# S3C_MuxJTAG.net
KiCad netlist of a schematic drawn in Altium Designer
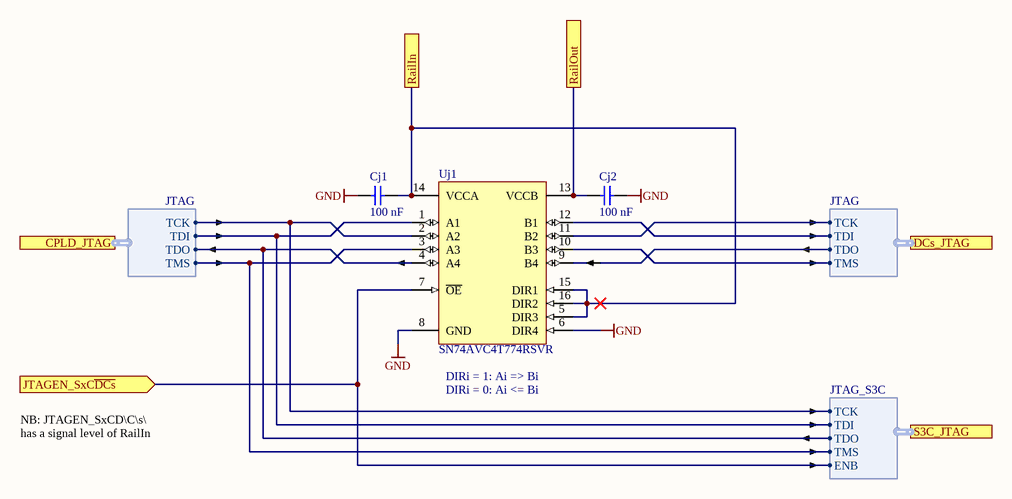
[diagram p0: S3C_MuxJTAG.SchDoc]

(export (version "E")
  (design (tool "Eeschema 10.0.6"))
  (components
    (comp (ref "Cj1")
      (value "100 nF")
      (footprint "C_0603_TE")
      (description "Generic capacitor")
      (fields
        (field (name "TOLERANCE") "10 %")
        (field (name "VOLTAGE") "50 V")
        (field (name "CREATED FROM") "AGeiger")
      )
      (libsource (lib "user") (part "CAP-NP"))
    )
    (comp (ref "Cj2")
      (value "100 nF")
      (footprint "C_0603_TE")
      (description "Generic capacitor")
      (fields
        (field (name "TOLERANCE") "10 %")
        (field (name "VOLTAGE") "50 V")
        (field (name "CREATED FROM") "AGeiger")
      )
      (libsource (lib "user") (part "CAP-NP"))
    )
    (comp (ref "Uj1")
      (value "SN74AVC4T774RSVR")
      (footprint "QFN40P260X180X55-16N")
      (fields
        (field (name "MANUFACTURER") "Texas Instruments")
        (field (name "LCSC PART NUMBER") "C779392")
        (field (name "CREATED FROM") "MGremer")
      )
      (libsource (lib "user") (part "SN74AVC4T774RSVR"))
    )
  )
  (nets
    (net (code "3") (name "/JTAGEN_SxC~{DCs}") (class "Default")
      (node (ref "Uj1") (pin "7") (pinfunction "~{OE}_7") (pintype "input"))
    )
    (net (code "4") (name "/RailIn") (class "Default")
      (node (ref "Cj1") (pin "1") (pinfunction "1_1") (pintype "passive"))
      (node (ref "Uj1") (pin "14") (pinfunction "VCCA_14") (pintype "power_in"))
      (node (ref "Uj1") (pin "15") (pinfunction "DIR1_15") (pintype "input"))
      (node (ref "Uj1") (pin "16") (pinfunction "DIR2_16") (pintype "input"))
      (node (ref "Uj1") (pin "5") (pinfunction "DIR3_5") (pintype "input"))
    )
    (net (code "5") (name "/RailOut") (class "Default")
      (node (ref "Cj2") (pin "2") (pinfunction "2_2") (pintype "passive"))
      (node (ref "Uj1") (pin "13") (pinfunction "VCCB_13") (pintype "power_in"))
    )
    (net (code "8") (name "GND") (class "Default")
      (node (ref "Cj1") (pin "2") (pinfunction "2_2") (pintype "passive"))
      (node (ref "Cj2") (pin "1") (pinfunction "1_1") (pintype "passive"))
      (node (ref "Uj1") (pin "6") (pinfunction "DIR4_6") (pintype "input"))
      (node (ref "Uj1") (pin "8") (pinfunction "GND_8") (pintype "power_in"))
    )
    (net (code "9") (name "unconnected-(Uj1-A1-Pad1)") (class "Default")
      (node (ref "Uj1") (pin "1") (pinfunction "A1_1") (pintype "bidirectional"))
    )
    (net (code "10") (name "unconnected-(Uj1-A2-Pad2)") (class "Default")
      (node (ref "Uj1") (pin "2") (pinfunction "A2_2") (pintype "bidirectional"))
    )
    (net (code "11") (name "unconnected-(Uj1-A3-Pad3)") (class "Default")
      (node (ref "Uj1") (pin "3") (pinfunction "A3_3") (pintype "bidirectional"))
    )
    (net (code "12") (name "unconnected-(Uj1-A4-Pad4)") (class "Default")
      (node (ref "Uj1") (pin "4") (pinfunction "A4_4") (pintype "bidirectional"))
    )
    (net (code "13") (name "unconnected-(Uj1-B1-Pad12)") (class "Default")
      (node (ref "Uj1") (pin "12") (pinfunction "B1_12") (pintype "bidirectional"))
    )
    (net (code "14") (name "unconnected-(Uj1-B2-Pad11)") (class "Default")
      (node (ref "Uj1") (pin "11") (pinfunction "B2_11") (pintype "bidirectional"))
    )
    (net (code "15") (name "unconnected-(Uj1-B3-Pad10)") (class "Default")
      (node (ref "Uj1") (pin "10") (pinfunction "B3_10") (pintype "bidirectional"))
    )
    (net (code "16") (name "unconnected-(Uj1-B4-Pad9)") (class "Default")
      (node (ref "Uj1") (pin "9") (pinfunction "B4_9") (pintype "bidirectional"))
    )
  )
)
